# TinyCam_Carrier_Board.net
KiCad netlist of a schematic drawn in EAGLE
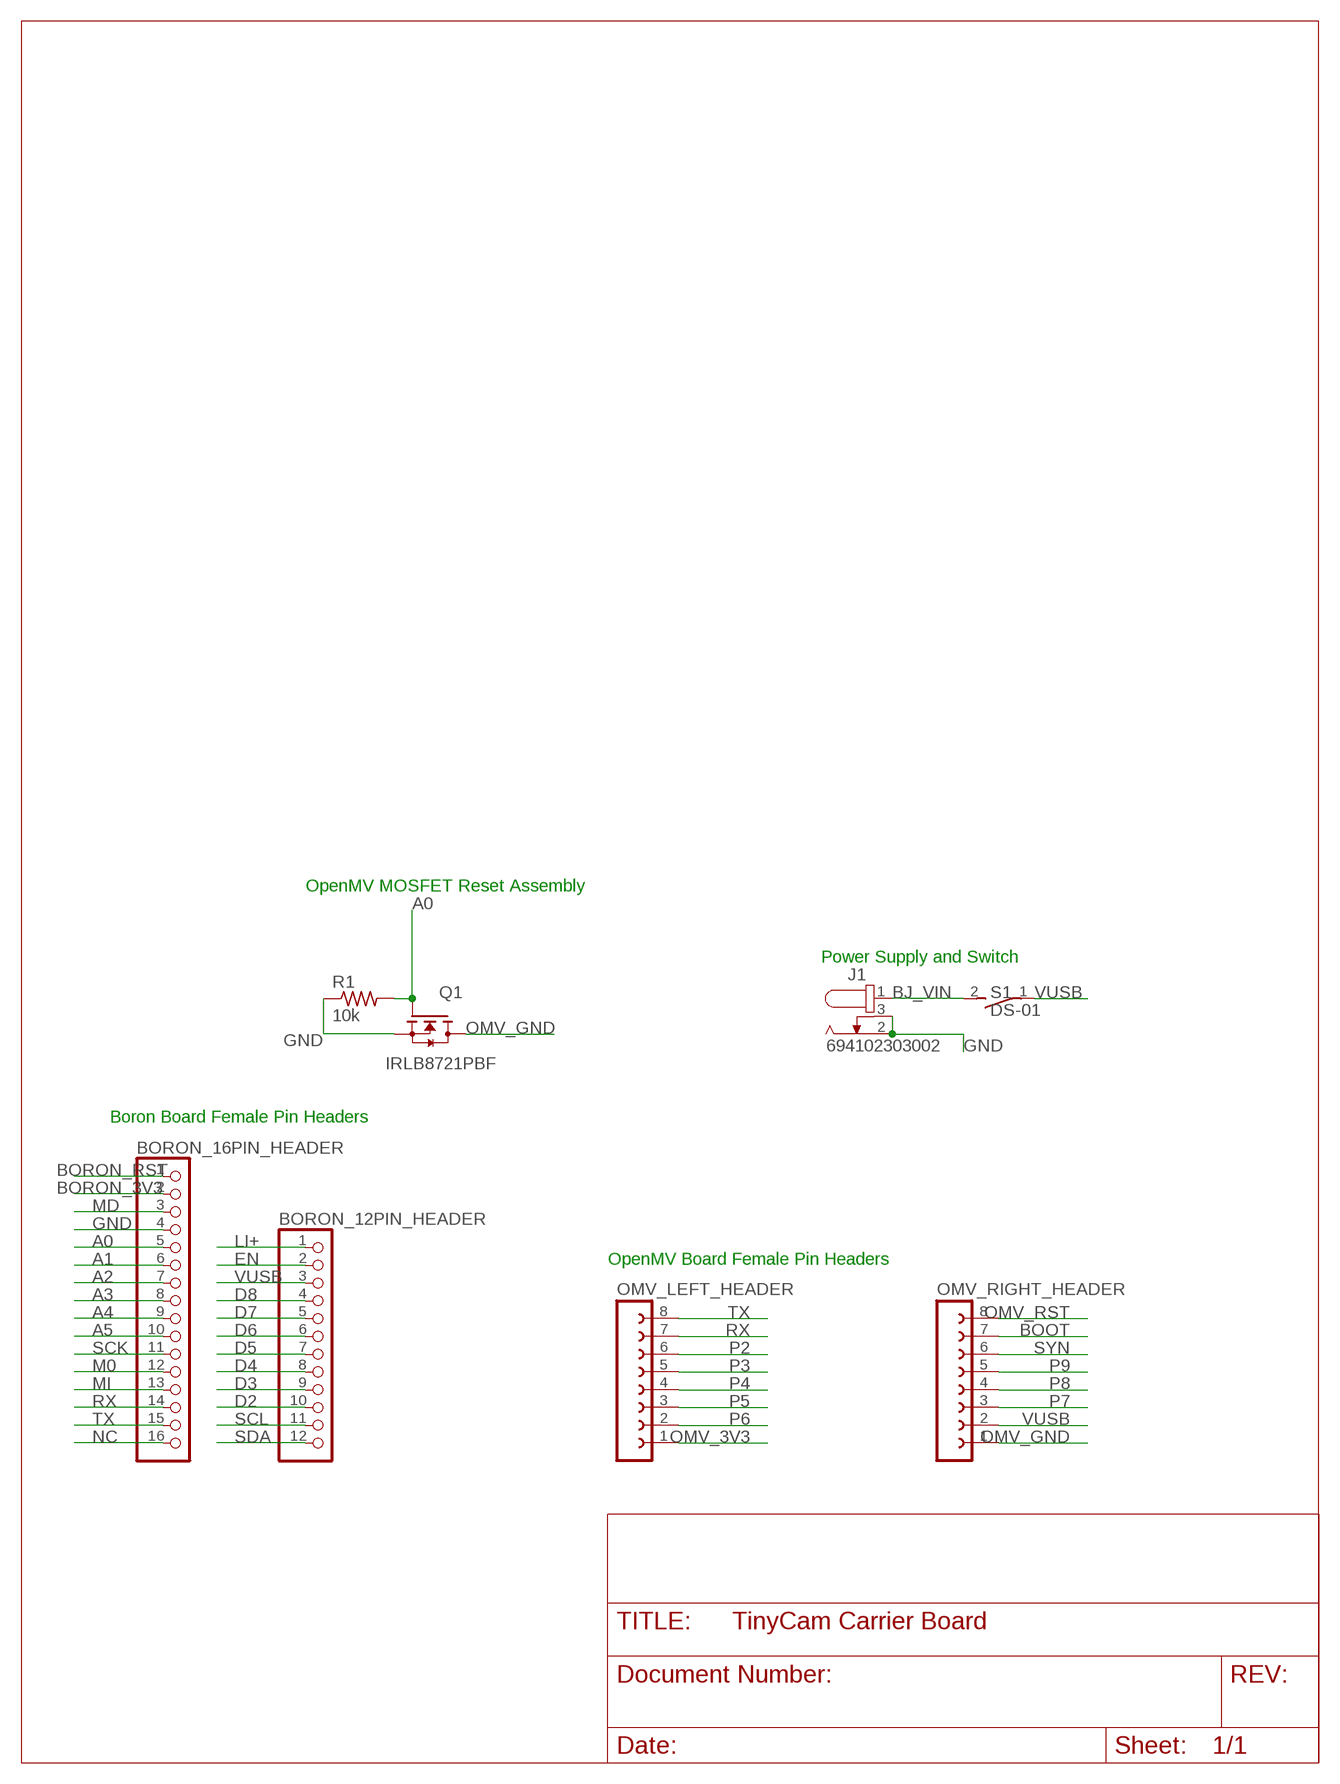
[diagram p0: schematic, sheet 1]

(export (version "E")
  (design (tool "Eeschema 10.0.6"))
  (components
    (comp (ref "BORON_12PIN_HEADER")
      (value "PINHD-1X12")
      (footprint "eagle-import:1X12")
      (libsource (lib "eagle-import") (part "PINHD-1X12"))
    )
    (comp (ref "BORON_16PIN_HEADER")
      (value "PINHD-1X16")
      (footprint "eagle-import:1X16")
      (libsource (lib "eagle-import") (part "PINHD-1X16"))
    )
    (comp (ref "J1")
      (value "694102303002")
      (footprint "eagle-import:694102303002")
      (libsource (lib "eagle-import") (part "694102303002"))
    )
    (comp (ref "OMV_LEFT_HEADER")
      (value "FE08-1")
      (footprint "eagle-import:FE08")
      (libsource (lib "eagle-import") (part "FE08-1"))
    )
    (comp (ref "OMV_RIGHT_HEADER")
      (value "FE08-1")
      (footprint "eagle-import:FE08")
      (libsource (lib "eagle-import") (part "FE08-1"))
    )
    (comp (ref "Q1")
      (value "IRLB8721PBF")
      (footprint "eagle-import:TO254P1067X483X2057-3")
      (fields
        (field (name "DIGIKEY_PART_NUMBER") "IRLB8721PBF-ND")
        (field (name "MF") "Infineon Technologies")
      )
      (libsource (lib "eagle-import") (part "IRLB8721PBF"))
    )
    (comp (ref "R1")
      (value "10k")
      (footprint "eagle-import:0204_7")
      (libsource (lib "eagle-import") (part "R-US_0204/7"))
    )
    (comp (ref "S1")
      (value "DS-01")
      (footprint "eagle-import:DS-01")
      (libsource (lib "eagle-import") (part "DS01E"))
    )
  )
  (nets
    (net (code "1") (name "/A0") (class "Default")
      (node (ref "BORON_16PIN_HEADER") (pin "5") (pinfunction "5_5") (pintype "passive"))
      (node (ref "Q1") (pin "1") (pinfunction "G_1") (pintype "passive"))
      (node (ref "R1") (pin "2") (pinfunction "2_2") (pintype "passive"))
    )
    (net (code "2") (name "/A1") (class "Default")
      (node (ref "BORON_16PIN_HEADER") (pin "6") (pinfunction "6_6") (pintype "passive"))
    )
    (net (code "3") (name "/A2") (class "Default")
      (node (ref "BORON_16PIN_HEADER") (pin "7") (pinfunction "7_7") (pintype "passive"))
    )
    (net (code "4") (name "/A3") (class "Default")
      (node (ref "BORON_16PIN_HEADER") (pin "8") (pinfunction "8_8") (pintype "passive"))
    )
    (net (code "5") (name "/A4") (class "Default")
      (node (ref "BORON_16PIN_HEADER") (pin "9") (pinfunction "9_9") (pintype "passive"))
    )
    (net (code "6") (name "/A5") (class "Default")
      (node (ref "BORON_16PIN_HEADER") (pin "10") (pinfunction "10_10") (pintype "passive"))
    )
    (net (code "7") (name "/BJ_VIN") (class "Default")
      (node (ref "J1") (pin "1") (pinfunction "1_1") (pintype "passive"))
      (node (ref "S1") (pin "2") (pinfunction "2_2") (pintype "passive"))
    )
    (net (code "8") (name "/BOOT") (class "Default")
      (node (ref "OMV_RIGHT_HEADER") (pin "7") (pinfunction "7_7") (pintype "passive"))
    )
    (net (code "9") (name "/BORON_3V3") (class "Default")
      (node (ref "BORON_16PIN_HEADER") (pin "2") (pinfunction "2_2") (pintype "passive"))
    )
    (net (code "10") (name "/BORON_RST") (class "Default")
      (node (ref "BORON_16PIN_HEADER") (pin "1") (pinfunction "1_1") (pintype "passive"))
    )
    (net (code "11") (name "/D2") (class "Default")
      (node (ref "BORON_12PIN_HEADER") (pin "10") (pinfunction "10_10") (pintype "passive"))
    )
    (net (code "12") (name "/D3") (class "Default")
      (node (ref "BORON_12PIN_HEADER") (pin "9") (pinfunction "9_9") (pintype "passive"))
    )
    (net (code "13") (name "/D4") (class "Default")
      (node (ref "BORON_12PIN_HEADER") (pin "8") (pinfunction "8_8") (pintype "passive"))
    )
    (net (code "14") (name "/D5") (class "Default")
      (node (ref "BORON_12PIN_HEADER") (pin "7") (pinfunction "7_7") (pintype "passive"))
    )
    (net (code "15") (name "/D6") (class "Default")
      (node (ref "BORON_12PIN_HEADER") (pin "6") (pinfunction "6_6") (pintype "passive"))
    )
    (net (code "16") (name "/D7") (class "Default")
      (node (ref "BORON_12PIN_HEADER") (pin "5") (pinfunction "5_5") (pintype "passive"))
    )
    (net (code "17") (name "/D8") (class "Default")
      (node (ref "BORON_12PIN_HEADER") (pin "4") (pinfunction "4_4") (pintype "passive"))
    )
    (net (code "18") (name "/EN") (class "Default")
      (node (ref "BORON_12PIN_HEADER") (pin "2") (pinfunction "2_2") (pintype "passive"))
    )
    (net (code "19") (name "/GND") (class "Default")
      (node (ref "BORON_16PIN_HEADER") (pin "4") (pinfunction "4_4") (pintype "passive"))
      (node (ref "J1") (pin "2") (pinfunction "2_2") (pintype "passive"))
      (node (ref "J1") (pin "3") (pinfunction "3_3") (pintype "passive"))
      (node (ref "Q1") (pin "3") (pinfunction "S_3") (pintype "passive"))
      (node (ref "R1") (pin "1") (pinfunction "1_1") (pintype "passive"))
    )
    (net (code "20") (name "/LI+") (class "Default")
      (node (ref "BORON_12PIN_HEADER") (pin "1") (pinfunction "1_1") (pintype "passive"))
    )
    (net (code "21") (name "/M0") (class "Default")
      (node (ref "BORON_16PIN_HEADER") (pin "12") (pinfunction "12_12") (pintype "passive"))
    )
    (net (code "22") (name "/MD") (class "Default")
      (node (ref "BORON_16PIN_HEADER") (pin "3") (pinfunction "3_3") (pintype "passive"))
    )
    (net (code "23") (name "/MI") (class "Default")
      (node (ref "BORON_16PIN_HEADER") (pin "13") (pinfunction "13_13") (pintype "passive"))
    )
    (net (code "24") (name "/NC") (class "Default")
      (node (ref "BORON_16PIN_HEADER") (pin "16") (pinfunction "16_16") (pintype "passive"))
    )
    (net (code "25") (name "/OMV_3V3") (class "Default")
      (node (ref "OMV_LEFT_HEADER") (pin "1") (pinfunction "1_1") (pintype "passive"))
    )
    (net (code "26") (name "/OMV_GND") (class "Default")
      (node (ref "OMV_RIGHT_HEADER") (pin "1") (pinfunction "1_1") (pintype "passive"))
      (node (ref "Q1") (pin "2") (pinfunction "D_2") (pintype "passive"))
    )
    (net (code "27") (name "/OMV_RST") (class "Default")
      (node (ref "OMV_RIGHT_HEADER") (pin "8") (pinfunction "8_8") (pintype "passive"))
    )
    (net (code "28") (name "/P2") (class "Default")
      (node (ref "OMV_LEFT_HEADER") (pin "6") (pinfunction "6_6") (pintype "passive"))
    )
    (net (code "29") (name "/P3") (class "Default")
      (node (ref "OMV_LEFT_HEADER") (pin "5") (pinfunction "5_5") (pintype "passive"))
    )
    (net (code "30") (name "/P4") (class "Default")
      (node (ref "OMV_LEFT_HEADER") (pin "4") (pinfunction "4_4") (pintype "passive"))
    )
    (net (code "31") (name "/P5") (class "Default")
      (node (ref "OMV_LEFT_HEADER") (pin "3") (pinfunction "3_3") (pintype "passive"))
    )
    (net (code "32") (name "/P6") (class "Default")
      (node (ref "OMV_LEFT_HEADER") (pin "2") (pinfunction "2_2") (pintype "passive"))
    )
    (net (code "33") (name "/P7") (class "Default")
      (node (ref "OMV_RIGHT_HEADER") (pin "3") (pinfunction "3_3") (pintype "passive"))
    )
    (net (code "34") (name "/P8") (class "Default")
      (node (ref "OMV_RIGHT_HEADER") (pin "4") (pinfunction "4_4") (pintype "passive"))
    )
    (net (code "35") (name "/P9") (class "Default")
      (node (ref "OMV_RIGHT_HEADER") (pin "5") (pinfunction "5_5") (pintype "passive"))
    )
    (net (code "36") (name "/RX") (class "Default")
      (node (ref "BORON_16PIN_HEADER") (pin "14") (pinfunction "14_14") (pintype "passive"))
      (node (ref "OMV_LEFT_HEADER") (pin "7") (pinfunction "7_7") (pintype "passive"))
    )
    (net (code "37") (name "/SCK") (class "Default")
      (node (ref "BORON_16PIN_HEADER") (pin "11") (pinfunction "11_11") (pintype "passive"))
    )
    (net (code "38") (name "/SCL") (class "Default")
      (node (ref "BORON_12PIN_HEADER") (pin "11") (pinfunction "11_11") (pintype "passive"))
    )
    (net (code "39") (name "/SDA") (class "Default")
      (node (ref "BORON_12PIN_HEADER") (pin "12") (pinfunction "12_12") (pintype "passive"))
    )
    (net (code "40") (name "/SYN") (class "Default")
      (node (ref "OMV_RIGHT_HEADER") (pin "6") (pinfunction "6_6") (pintype "passive"))
    )
    (net (code "41") (name "/TX") (class "Default")
      (node (ref "BORON_16PIN_HEADER") (pin "15") (pinfunction "15_15") (pintype "passive"))
      (node (ref "OMV_LEFT_HEADER") (pin "8") (pinfunction "8_8") (pintype "passive"))
    )
    (net (code "42") (name "/VUSB") (class "Default")
      (node (ref "BORON_12PIN_HEADER") (pin "3") (pinfunction "3_3") (pintype "passive"))
      (node (ref "OMV_RIGHT_HEADER") (pin "2") (pinfunction "2_2") (pintype "passive"))
      (node (ref "S1") (pin "1") (pinfunction "1_1") (pintype "passive"))
    )
  )
)
